# Main.net
KiCad netlist of a schematic drawn in Altium Designer
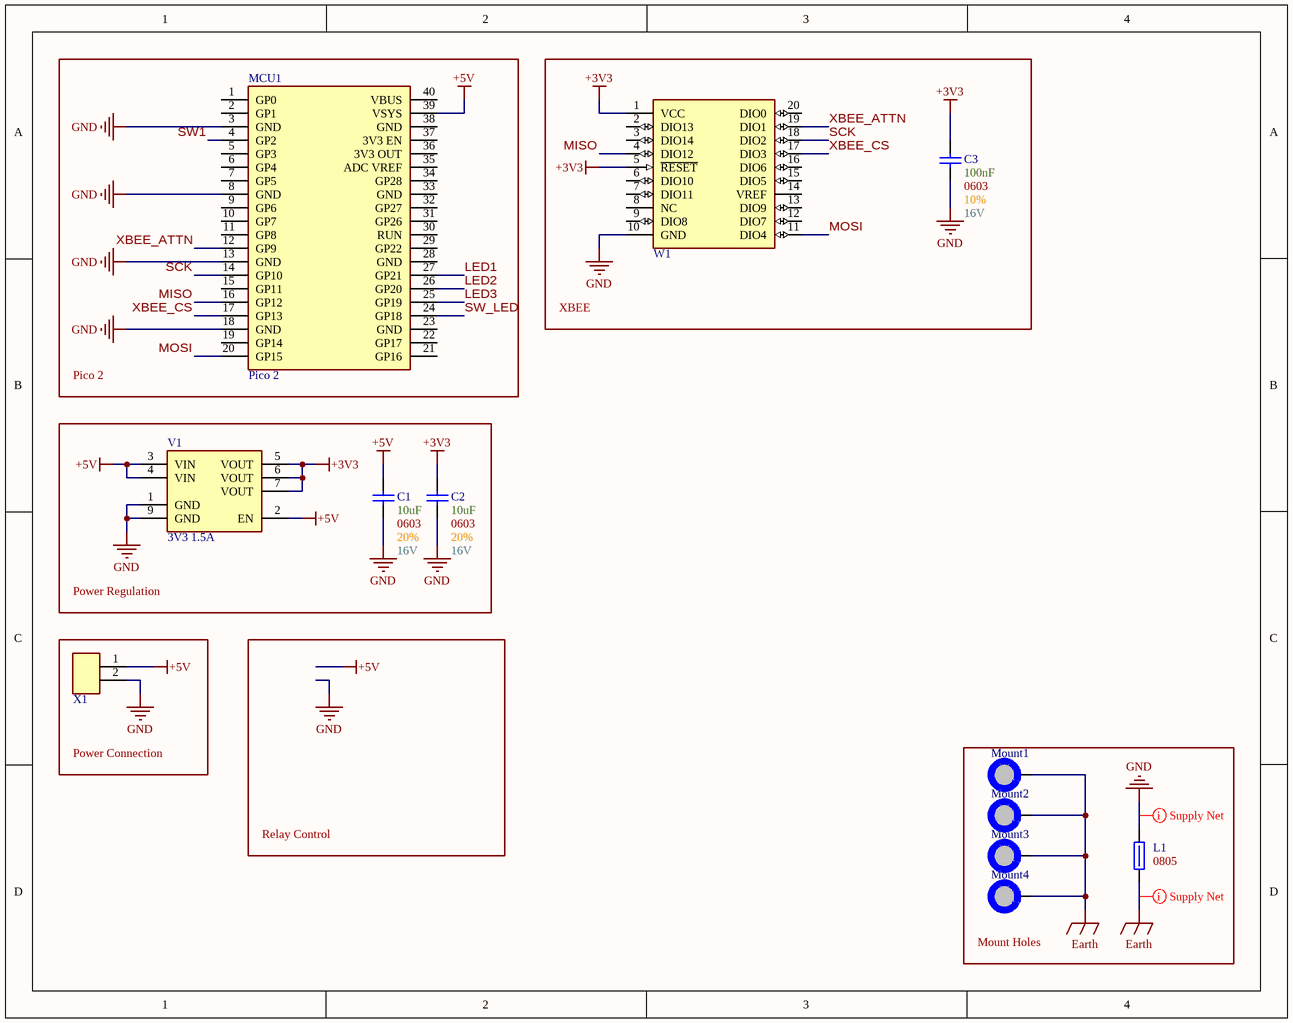
[diagram p0: Main.SchDoc]

(export (version "E")
  (design (tool "Eeschema 10.0.6"))
  (components
    (comp (ref "C1")
      (value "[Cap] 0603 10uF 20% 16V")
      (footprint "[Cap] SMD 0603")
      (description "GRM188C81C106MA73D")
      (fields
        (field (name "MAX VOLTAGE") "16V")
        (field (name "SIZE PACKAGE") "0603")
        (field (name "TOLERANCE") "20%")
        (field (name "CAPACITANCE") "10uF")
      )
      (libsource (lib "Capacitors") (part "[Cap] 0603 10uF 20% 16V"))
    )
    (comp (ref "C2")
      (value "[Cap] 0603 10uF 20% 16V")
      (footprint "[Cap] SMD 0603")
      (description "GRM188C81C106MA73D")
      (fields
        (field (name "MAX VOLTAGE") "16V")
        (field (name "SIZE PACKAGE") "0603")
        (field (name "TOLERANCE") "20%")
        (field (name "CAPACITANCE") "10uF")
      )
      (libsource (lib "Capacitors") (part "[Cap] 0603 10uF 20% 16V"))
    )
    (comp (ref "C3")
      (value "[Cap] 0603 0.1uF 10% 16V")
      (footprint "[Cap] SMD 0603")
      (description "CC0603KRX7R7BB104")
      (fields
        (field (name "MAX VOLTAGE") "16V")
        (field (name "SIZE PACKAGE") "0603")
        (field (name "TOLERANCE") "10%")
        (field (name "CAPACITANCE") "100nF")
      )
      (libsource (lib "Capacitors") (part "[Cap] 0603 0.1uF 10% 16V"))
    )
    (comp (ref "L1")
      (value "652-MH2029-300Y")
      (footprint "[Ferrite] SMD 0805")
      (fields (field (name "SIZE PACKAGE") "0805"))
      (libsource (lib "Ferrite Beads") (part "[Ferrite] SMD 0805 3A 30ohm"))
    )
    (comp (ref "MCU1")
      (value "Pico 2")
      (footprint "[Pi] Pico 2")
      (description "SC1631")
      (libsource (lib "Devices") (part "[Pi] Pico 2"))
    )
    (comp (ref "Mount1")
      (value "M3 Mount Hole")
      (footprint "[Mount] M3 Mount Hole")
      (description "Place at least 4.5mm from board edge. Plated.")
      (libsource (lib "Misc Components") (part "[Mount] M3 Mount Hole"))
    )
    (comp (ref "Mount2")
      (value "M3 Mount Hole")
      (footprint "[Mount] M3 Mount Hole")
      (description "Place at least 4.5mm from board edge. Plated.")
      (libsource (lib "Misc Components") (part "[Mount] M3 Mount Hole"))
    )
    (comp (ref "Mount3")
      (value "M3 Mount Hole")
      (footprint "[Mount] M3 Mount Hole")
      (description "Place at least 4.5mm from board edge. Plated.")
      (libsource (lib "Misc Components") (part "[Mount] M3 Mount Hole"))
    )
    (comp (ref "Mount4")
      (value "M3 Mount Hole")
      (footprint "[Mount] M3 Mount Hole")
      (description "Place at least 4.5mm from board edge. Plated.")
      (libsource (lib "Misc Components") (part "[Mount] M3 Mount Hole"))
    )
    (comp (ref "V1")
      (value "3V3 1.5A")
      (footprint "[Linear] 3V3 1.5A")
      (description "AP7362A-33SP-13")
      (libsource (lib "Voltage Regulators") (part "[Linear] 3V3 1.5A"))
    )
    (comp (ref "W1")
      (value "[XBEE] 900HP")
      (footprint "[XBEE] 900HP")
      (description "XBP9B-DMST-002")
      (libsource (lib "Devices") (part "[XBEE] 900HP"))
    )
    (comp (ref "X1")
      (value "[Sherlock] 2pin")
      (footprint "[Sherlock] 2pin")
      (description "0353620250")
      (libsource (lib "Connectors") (part "[Sherlock] 2pin"))
    )
  )
  (nets
    (net (code "1") (name "+3V3") (class "Default")
      (node (ref "C2") (pin "2") (pinfunction "2_2") (pintype "passive"))
      (node (ref "C3") (pin "2") (pinfunction "2_2") (pintype "passive"))
      (node (ref "V1") (pin "5") (pinfunction "VOUT_5") (pintype "passive"))
      (node (ref "V1") (pin "6") (pinfunction "VOUT_6") (pintype "passive"))
      (node (ref "V1") (pin "7") (pinfunction "VOUT_7") (pintype "passive"))
      (node (ref "W1") (pin "1") (pinfunction "VCC_1") (pintype "power_in"))
      (node (ref "W1") (pin "5") (pinfunction "RESET_5") (pintype "input"))
    )
    (net (code "2") (name "+5V") (class "Default")
      (node (ref "C1") (pin "2") (pinfunction "2_2") (pintype "passive"))
      (node (ref "MCU1") (pin "39") (pinfunction "VSYS_39") (pintype "passive"))
      (node (ref "V1") (pin "2") (pinfunction "EN_2") (pintype "passive"))
      (node (ref "V1") (pin "3") (pinfunction "VIN_3") (pintype "passive"))
      (node (ref "V1") (pin "4") (pinfunction "VIN_4") (pintype "passive"))
      (node (ref "X1") (pin "1") (pintype "passive"))
    )
    (net (code "3") (name "/LED1") (class "Default")
      (node (ref "MCU1") (pin "27") (pinfunction "GP21_27") (pintype "passive"))
    )
    (net (code "4") (name "/LED2") (class "Default")
      (node (ref "MCU1") (pin "26") (pinfunction "GP20_26") (pintype "passive"))
    )
    (net (code "5") (name "/LED3") (class "Default")
      (node (ref "MCU1") (pin "25") (pinfunction "GP19_25") (pintype "passive"))
    )
    (net (code "6") (name "/MISO") (class "Default")
      (node (ref "MCU1") (pin "16") (pinfunction "GP12_16") (pintype "passive"))
      (node (ref "W1") (pin "4") (pinfunction "DIO12_4") (pintype "bidirectional"))
    )
    (net (code "7") (name "/MOSI") (class "Default")
      (node (ref "MCU1") (pin "20") (pinfunction "GP15_20") (pintype "passive"))
      (node (ref "W1") (pin "11") (pinfunction "DIO4_11") (pintype "bidirectional"))
    )
    (net (code "8") (name "/SCK") (class "Default")
      (node (ref "MCU1") (pin "14") (pinfunction "GP10_14") (pintype "passive"))
      (node (ref "W1") (pin "18") (pinfunction "DIO2_18") (pintype "bidirectional"))
    )
    (net (code "9") (name "/SW1") (class "Default")
      (node (ref "MCU1") (pin "4") (pinfunction "GP2_4") (pintype "passive"))
    )
    (net (code "10") (name "/SW_LED") (class "Default")
      (node (ref "MCU1") (pin "24") (pinfunction "GP18_24") (pintype "passive"))
    )
    (net (code "11") (name "/XBEE_ATTN") (class "Default")
      (node (ref "MCU1") (pin "12") (pinfunction "GP9_12") (pintype "passive"))
      (node (ref "W1") (pin "19") (pinfunction "DIO1_19") (pintype "bidirectional"))
    )
    (net (code "12") (name "/XBEE_CS") (class "Default")
      (node (ref "MCU1") (pin "17") (pinfunction "GP13_17") (pintype "passive"))
      (node (ref "W1") (pin "17") (pinfunction "DIO3_17") (pintype "bidirectional"))
    )
    (net (code "13") (name "Earth") (class "Default")
      (node (ref "L1") (pin "1") (pinfunction "1_1") (pintype "passive"))
      (node (ref "Mount1") (pin "1") (pintype "power_in"))
      (node (ref "Mount2") (pin "1") (pintype "power_in"))
      (node (ref "Mount3") (pin "1") (pintype "power_in"))
      (node (ref "Mount4") (pin "1") (pintype "power_in"))
    )
    (net (code "14") (name "GND") (class "Default")
      (node (ref "C1") (pin "1") (pinfunction "1_1") (pintype "passive"))
      (node (ref "C2") (pin "1") (pinfunction "1_1") (pintype "passive"))
      (node (ref "C3") (pin "1") (pinfunction "1_1") (pintype "passive"))
      (node (ref "L1") (pin "2") (pinfunction "2_2") (pintype "passive"))
      (node (ref "MCU1") (pin "13") (pinfunction "GND_13") (pintype "passive"))
      (node (ref "MCU1") (pin "18") (pinfunction "GND_18") (pintype "passive"))
      (node (ref "MCU1") (pin "3") (pinfunction "GND_3") (pintype "passive"))
      (node (ref "MCU1") (pin "8") (pinfunction "GND_8") (pintype "passive"))
      (node (ref "V1") (pin "1") (pinfunction "GND_1") (pintype "passive"))
      (node (ref "V1") (pin "9") (pinfunction "GND_9") (pintype "passive"))
      (node (ref "W1") (pin "10") (pinfunction "GND_10") (pintype "power_in"))
      (node (ref "X1") (pin "2") (pintype "passive"))
    )
    (net (code "15") (name "unconnected-(MCU1-3V3_EN-Pad37)") (class "Default")
      (node (ref "MCU1") (pin "37") (pinfunction "3V3_EN_37") (pintype "passive"))
    )
    (net (code "16") (name "unconnected-(MCU1-3V3_OUT-Pad36)") (class "Default")
      (node (ref "MCU1") (pin "36") (pinfunction "3V3_OUT_36") (pintype "passive"))
    )
    (net (code "17") (name "unconnected-(MCU1-ADC_VREF-Pad35)") (class "Default")
      (node (ref "MCU1") (pin "35") (pinfunction "ADC_VREF_35") (pintype "passive"))
    )
    (net (code "18") (name "unconnected-(MCU1-GND-Pad23)") (class "Default")
      (node (ref "MCU1") (pin "23") (pinfunction "GND_23") (pintype "passive"))
    )
    (net (code "19") (name "unconnected-(MCU1-GND-Pad28)") (class "Default")
      (node (ref "MCU1") (pin "28") (pinfunction "GND_28") (pintype "passive"))
    )
    (net (code "20") (name "unconnected-(MCU1-GND-Pad33)") (class "Default")
      (node (ref "MCU1") (pin "33") (pinfunction "GND_33") (pintype "passive"))
    )
    (net (code "21") (name "unconnected-(MCU1-GND-Pad38)") (class "Default")
      (node (ref "MCU1") (pin "38") (pinfunction "GND_38") (pintype "passive"))
    )
    (net (code "22") (name "unconnected-(MCU1-GP0-Pad1)") (class "Default")
      (node (ref "MCU1") (pin "1") (pinfunction "GP0_1") (pintype "passive"))
    )
    (net (code "23") (name "unconnected-(MCU1-GP1-Pad2)") (class "Default")
      (node (ref "MCU1") (pin "2") (pinfunction "GP1_2") (pintype "passive"))
    )
    (net (code "24") (name "unconnected-(MCU1-GP3-Pad5)") (class "Default")
      (node (ref "MCU1") (pin "5") (pinfunction "GP3_5") (pintype "passive"))
    )
    (net (code "25") (name "unconnected-(MCU1-GP4-Pad6)") (class "Default")
      (node (ref "MCU1") (pin "6") (pinfunction "GP4_6") (pintype "passive"))
    )
    (net (code "26") (name "unconnected-(MCU1-GP5-Pad7)") (class "Default")
      (node (ref "MCU1") (pin "7") (pinfunction "GP5_7") (pintype "passive"))
    )
    (net (code "27") (name "unconnected-(MCU1-GP6-Pad9)") (class "Default")
      (node (ref "MCU1") (pin "9") (pinfunction "GP6_9") (pintype "passive"))
    )
    (net (code "28") (name "unconnected-(MCU1-GP7-Pad10)") (class "Default")
      (node (ref "MCU1") (pin "10") (pinfunction "GP7_10") (pintype "passive"))
    )
    (net (code "29") (name "unconnected-(MCU1-GP8-Pad11)") (class "Default")
      (node (ref "MCU1") (pin "11") (pinfunction "GP8_11") (pintype "passive"))
    )
    (net (code "30") (name "unconnected-(MCU1-GP11-Pad15)") (class "Default")
      (node (ref "MCU1") (pin "15") (pinfunction "GP11_15") (pintype "passive"))
    )
    (net (code "31") (name "unconnected-(MCU1-GP14-Pad19)") (class "Default")
      (node (ref "MCU1") (pin "19") (pinfunction "GP14_19") (pintype "passive"))
    )
    (net (code "32") (name "unconnected-(MCU1-GP16-Pad21)") (class "Default")
      (node (ref "MCU1") (pin "21") (pinfunction "GP16_21") (pintype "passive"))
    )
    (net (code "33") (name "unconnected-(MCU1-GP17-Pad22)") (class "Default")
      (node (ref "MCU1") (pin "22") (pinfunction "GP17_22") (pintype "passive"))
    )
    (net (code "34") (name "unconnected-(MCU1-GP22-Pad29)") (class "Default")
      (node (ref "MCU1") (pin "29") (pinfunction "GP22_29") (pintype "passive"))
    )
    (net (code "35") (name "unconnected-(MCU1-GP26-Pad31)") (class "Default")
      (node (ref "MCU1") (pin "31") (pinfunction "GP26_31") (pintype "passive"))
    )
    (net (code "36") (name "unconnected-(MCU1-GP27-Pad32)") (class "Default")
      (node (ref "MCU1") (pin "32") (pinfunction "GP27_32") (pintype "passive"))
    )
    (net (code "37") (name "unconnected-(MCU1-GP28-Pad34)") (class "Default")
      (node (ref "MCU1") (pin "34") (pinfunction "GP28_34") (pintype "passive"))
    )
    (net (code "38") (name "unconnected-(MCU1-RUN-Pad30)") (class "Default")
      (node (ref "MCU1") (pin "30") (pinfunction "RUN_30") (pintype "passive"))
    )
    (net (code "39") (name "unconnected-(MCU1-VBUS-Pad40)") (class "Default")
      (node (ref "MCU1") (pin "40") (pinfunction "VBUS_40") (pintype "passive"))
    )
    (net (code "40") (name "unconnected-(W1-DIO0-Pad20)") (class "Default")
      (node (ref "W1") (pin "20") (pinfunction "DIO0_20") (pintype "bidirectional"))
    )
    (net (code "41") (name "unconnected-(W1-DIO5-Pad15)") (class "Default")
      (node (ref "W1") (pin "15") (pinfunction "DIO5_15") (pintype "bidirectional"))
    )
    (net (code "42") (name "unconnected-(W1-DIO6-Pad16)") (class "Default")
      (node (ref "W1") (pin "16") (pinfunction "DIO6_16") (pintype "bidirectional"))
    )
    (net (code "43") (name "unconnected-(W1-DIO7-Pad12)") (class "Default")
      (node (ref "W1") (pin "12") (pinfunction "DIO7_12") (pintype "bidirectional"))
    )
    (net (code "44") (name "unconnected-(W1-DIO8-Pad9)") (class "Default")
      (node (ref "W1") (pin "9") (pinfunction "DIO8_9") (pintype "bidirectional"))
    )
    (net (code "45") (name "unconnected-(W1-DIO9-Pad13)") (class "Default")
      (node (ref "W1") (pin "13") (pinfunction "DIO9_13") (pintype "bidirectional"))
    )
    (net (code "46") (name "unconnected-(W1-DIO10-Pad6)") (class "Default")
      (node (ref "W1") (pin "6") (pinfunction "DIO10_6") (pintype "bidirectional"))
    )
    (net (code "47") (name "unconnected-(W1-DIO11-Pad7)") (class "Default")
      (node (ref "W1") (pin "7") (pinfunction "DIO11_7") (pintype "bidirectional"))
    )
    (net (code "48") (name "unconnected-(W1-DIO13-Pad2)") (class "Default")
      (node (ref "W1") (pin "2") (pinfunction "DIO13_2") (pintype "bidirectional"))
    )
    (net (code "49") (name "unconnected-(W1-DIO14-Pad3)") (class "Default")
      (node (ref "W1") (pin "3") (pinfunction "DIO14_3") (pintype "bidirectional"))
    )
    (net (code "50") (name "unconnected-(W1-NC-Pad8)") (class "Default")
      (node (ref "W1") (pin "8") (pinfunction "NC_8") (pintype "passive"))
    )
    (net (code "51") (name "unconnected-(W1-VREF-Pad14)") (class "Default")
      (node (ref "W1") (pin "14") (pinfunction "VREF_14") (pintype "power_in"))
    )
  )
)
